# shelves_expander_v10.net
KiCad netlist of a schematic drawn in EAGLE
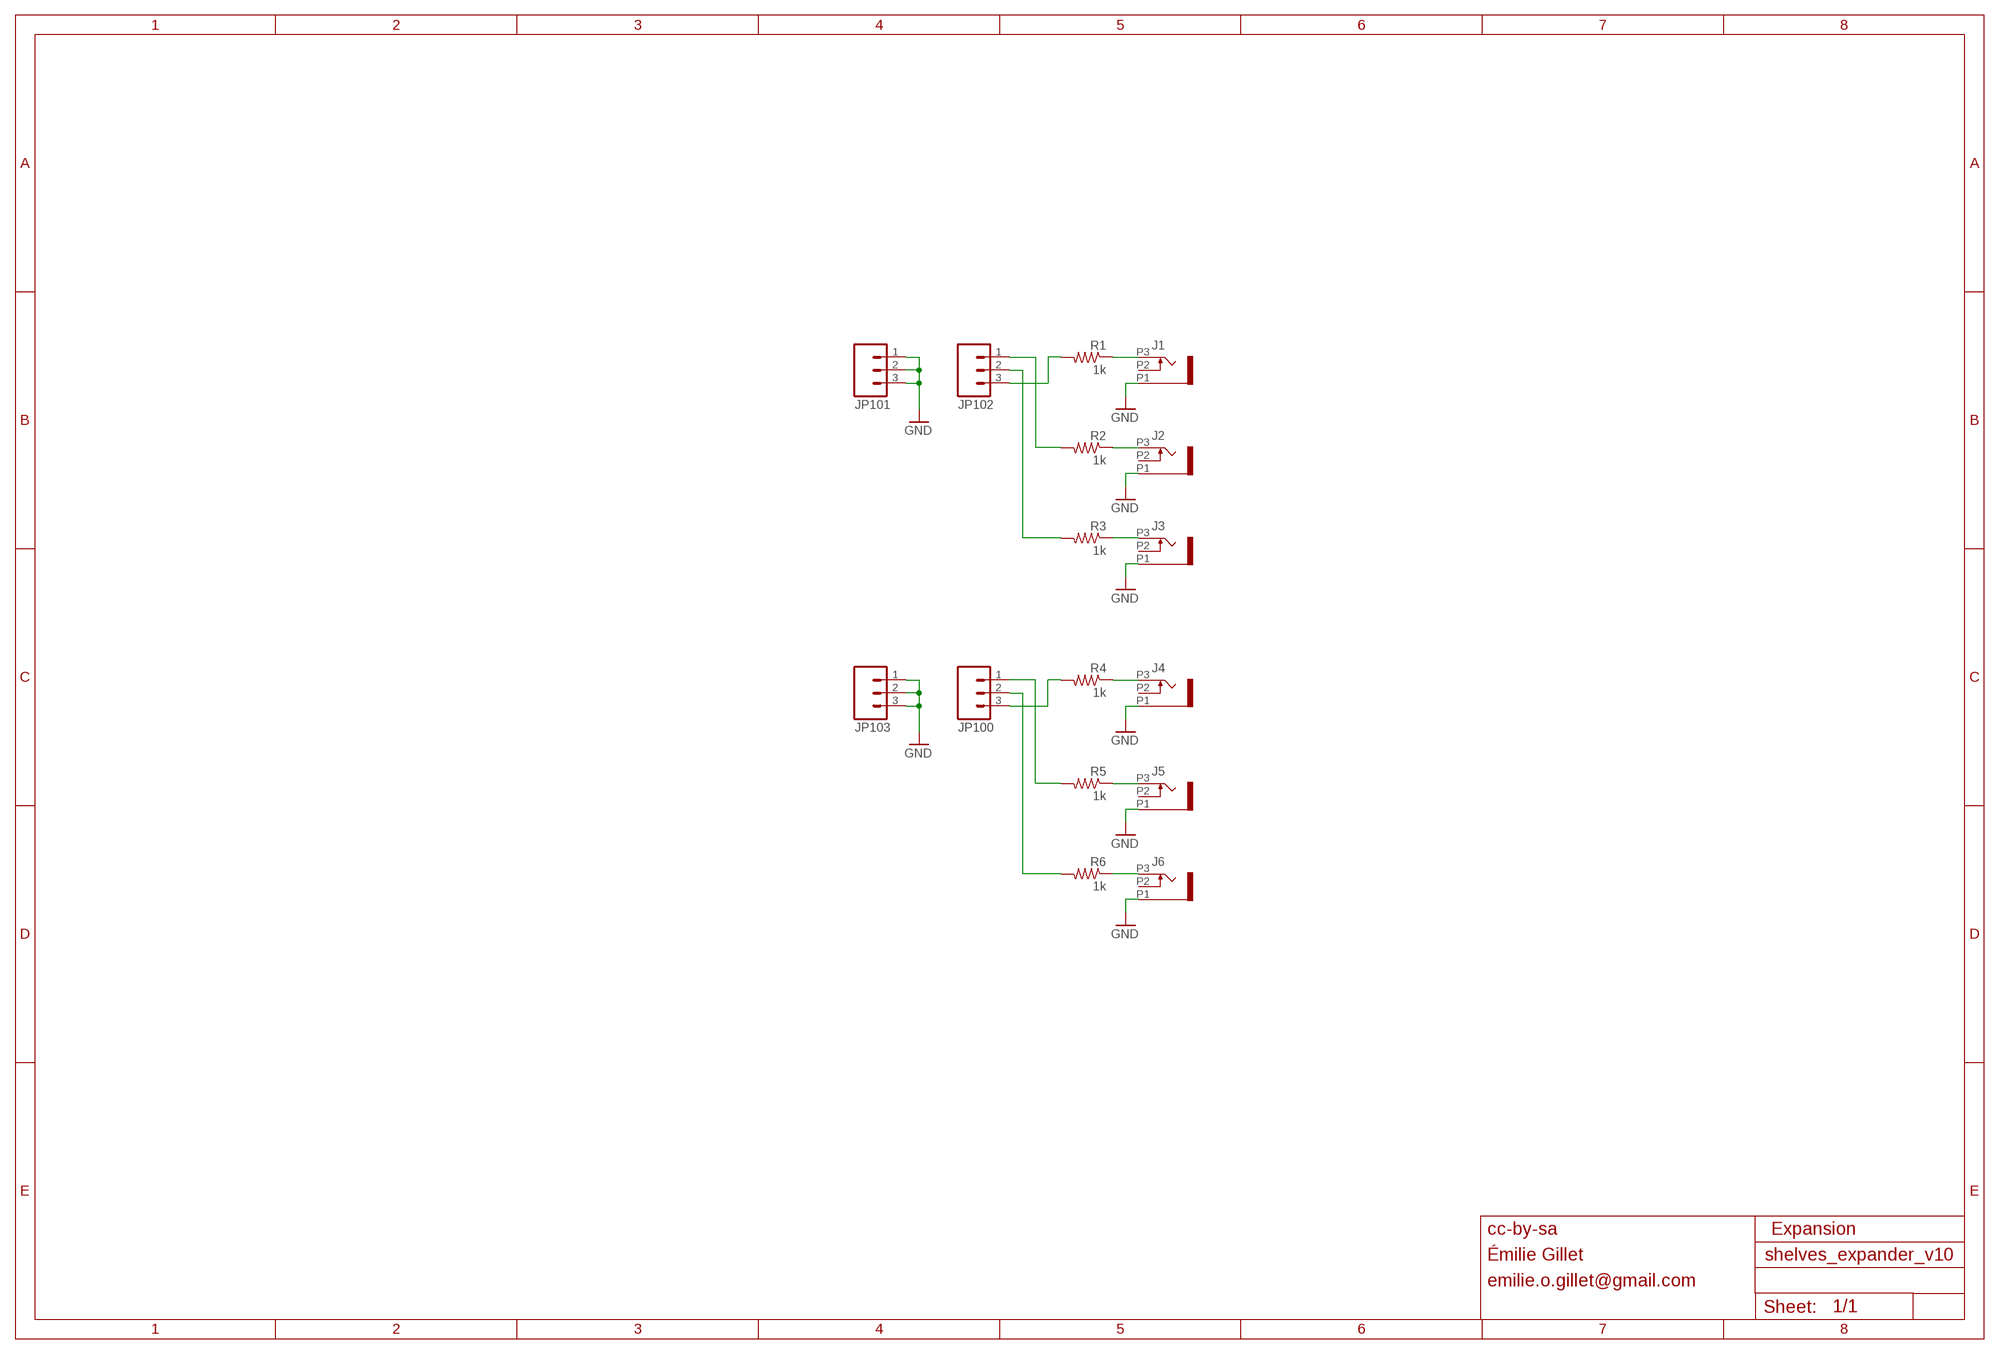
[diagram p0: schematic, sheet 1]

(export (version "E")
  (design (tool "Eeschema 10.0.6"))
  (components
    (comp (ref "J1")
      (value "PJ301_THONKICONN6")
      (footprint "eagle-import:WQP_PJ_301M6")
      (libsource (lib "eagle-import") (part "PJ301_THONKICONN6"))
    )
    (comp (ref "J2")
      (value "PJ301_THONKICONN6")
      (footprint "eagle-import:WQP_PJ_301M6")
      (libsource (lib "eagle-import") (part "PJ301_THONKICONN6"))
    )
    (comp (ref "J3")
      (value "PJ301_THONKICONN6")
      (footprint "eagle-import:WQP_PJ_301M6")
      (libsource (lib "eagle-import") (part "PJ301_THONKICONN6"))
    )
    (comp (ref "J4")
      (value "PJ301_THONKICONN6")
      (footprint "eagle-import:WQP_PJ_301M6")
      (libsource (lib "eagle-import") (part "PJ301_THONKICONN6"))
    )
    (comp (ref "J5")
      (value "PJ301_THONKICONN6")
      (footprint "eagle-import:WQP_PJ_301M6")
      (libsource (lib "eagle-import") (part "PJ301_THONKICONN6"))
    )
    (comp (ref "J6")
      (value "PJ301_THONKICONN6")
      (footprint "eagle-import:WQP_PJ_301M6")
      (libsource (lib "eagle-import") (part "PJ301_THONKICONN6"))
    )
    (comp (ref "JP100")
      (value "M03PTH")
      (footprint "eagle-import:1X03")
      (libsource (lib "eagle-import") (part "M03PTH"))
    )
    (comp (ref "JP101")
      (value "M03PTH")
      (footprint "eagle-import:1X03")
      (libsource (lib "eagle-import") (part "M03PTH"))
    )
    (comp (ref "JP102")
      (value "M03PTH")
      (footprint "eagle-import:1X03")
      (libsource (lib "eagle-import") (part "M03PTH"))
    )
    (comp (ref "JP103")
      (value "M03PTH")
      (footprint "eagle-import:1X03")
      (libsource (lib "eagle-import") (part "M03PTH"))
    )
    (comp (ref "R1")
      (value "1k")
      (footprint "eagle-import:R0603")
      (libsource (lib "eagle-import") (part "R-US_R0603"))
    )
    (comp (ref "R2")
      (value "1k")
      (footprint "eagle-import:R0603")
      (libsource (lib "eagle-import") (part "R-US_R0603"))
    )
    (comp (ref "R3")
      (value "1k")
      (footprint "eagle-import:R0603")
      (libsource (lib "eagle-import") (part "R-US_R0603"))
    )
    (comp (ref "R4")
      (value "1k")
      (footprint "eagle-import:R0603")
      (libsource (lib "eagle-import") (part "R-US_R0603"))
    )
    (comp (ref "R5")
      (value "1k")
      (footprint "eagle-import:R0603")
      (libsource (lib "eagle-import") (part "R-US_R0603"))
    )
    (comp (ref "R6")
      (value "1k")
      (footprint "eagle-import:R0603")
      (libsource (lib "eagle-import") (part "R-US_R0603"))
    )
  )
  (nets
    (net (code "1") (name "GND") (class "Default")
      (node (ref "J1") (pin "P1") (pinfunction "1_P1") (pintype "passive"))
      (node (ref "J2") (pin "P1") (pinfunction "1_P1") (pintype "passive"))
      (node (ref "J3") (pin "P1") (pinfunction "1_P1") (pintype "passive"))
      (node (ref "J4") (pin "P1") (pinfunction "1_P1") (pintype "passive"))
      (node (ref "J5") (pin "P1") (pinfunction "1_P1") (pintype "passive"))
      (node (ref "J6") (pin "P1") (pinfunction "1_P1") (pintype "passive"))
      (node (ref "JP101") (pin "1") (pinfunction "1_1") (pintype "passive"))
      (node (ref "JP101") (pin "2") (pinfunction "2_2") (pintype "passive"))
      (node (ref "JP101") (pin "3") (pinfunction "3_3") (pintype "passive"))
      (node (ref "JP103") (pin "1") (pinfunction "1_1") (pintype "passive"))
      (node (ref "JP103") (pin "2") (pinfunction "2_2") (pintype "passive"))
      (node (ref "JP103") (pin "3") (pinfunction "3_3") (pintype "passive"))
    )
    (net (code "2") (name "Net-(J1-3)") (class "Default")
      (node (ref "J1") (pin "P3") (pinfunction "3_P3") (pintype "passive"))
      (node (ref "R1") (pin "1") (pinfunction "1_1") (pintype "passive"))
    )
    (net (code "3") (name "Net-(J2-3)") (class "Default")
      (node (ref "J2") (pin "P3") (pinfunction "3_P3") (pintype "passive"))
      (node (ref "R2") (pin "1") (pinfunction "1_1") (pintype "passive"))
    )
    (net (code "4") (name "Net-(J3-3)") (class "Default")
      (node (ref "J3") (pin "P3") (pinfunction "3_P3") (pintype "passive"))
      (node (ref "R3") (pin "1") (pinfunction "1_1") (pintype "passive"))
    )
    (net (code "5") (name "Net-(J4-3)") (class "Default")
      (node (ref "J4") (pin "P3") (pinfunction "3_P3") (pintype "passive"))
      (node (ref "R4") (pin "1") (pinfunction "1_1") (pintype "passive"))
    )
    (net (code "6") (name "Net-(J5-3)") (class "Default")
      (node (ref "J5") (pin "P3") (pinfunction "3_P3") (pintype "passive"))
      (node (ref "R5") (pin "1") (pinfunction "1_1") (pintype "passive"))
    )
    (net (code "7") (name "Net-(J6-3)") (class "Default")
      (node (ref "J6") (pin "P3") (pinfunction "3_P3") (pintype "passive"))
      (node (ref "R6") (pin "1") (pinfunction "1_1") (pintype "passive"))
    )
    (net (code "8") (name "Net-(JP100-Pad1)") (class "Default")
      (node (ref "JP100") (pin "1") (pinfunction "1_1") (pintype "passive"))
      (node (ref "R5") (pin "2") (pinfunction "2_2") (pintype "passive"))
    )
    (net (code "9") (name "Net-(JP100-Pad2)") (class "Default")
      (node (ref "JP100") (pin "2") (pinfunction "2_2") (pintype "passive"))
      (node (ref "R6") (pin "2") (pinfunction "2_2") (pintype "passive"))
    )
    (net (code "10") (name "Net-(JP100-Pad3)") (class "Default")
      (node (ref "JP100") (pin "3") (pinfunction "3_3") (pintype "passive"))
      (node (ref "R4") (pin "2") (pinfunction "2_2") (pintype "passive"))
    )
    (net (code "11") (name "Net-(JP102-Pad1)") (class "Default")
      (node (ref "JP102") (pin "1") (pinfunction "1_1") (pintype "passive"))
      (node (ref "R2") (pin "2") (pinfunction "2_2") (pintype "passive"))
    )
    (net (code "12") (name "Net-(JP102-Pad2)") (class "Default")
      (node (ref "JP102") (pin "2") (pinfunction "2_2") (pintype "passive"))
      (node (ref "R3") (pin "2") (pinfunction "2_2") (pintype "passive"))
    )
    (net (code "13") (name "Net-(JP102-Pad3)") (class "Default")
      (node (ref "JP102") (pin "3") (pinfunction "3_3") (pintype "passive"))
      (node (ref "R1") (pin "2") (pinfunction "2_2") (pintype "passive"))
    )
    (net (code "14") (name "unconnected-(J1-2-PadP2)") (class "Default")
      (node (ref "J1") (pin "P2") (pinfunction "2_P2") (pintype "passive"))
    )
    (net (code "15") (name "unconnected-(J2-2-PadP2)") (class "Default")
      (node (ref "J2") (pin "P2") (pinfunction "2_P2") (pintype "passive"))
    )
    (net (code "16") (name "unconnected-(J3-2-PadP2)") (class "Default")
      (node (ref "J3") (pin "P2") (pinfunction "2_P2") (pintype "passive"))
    )
    (net (code "17") (name "unconnected-(J4-2-PadP2)") (class "Default")
      (node (ref "J4") (pin "P2") (pinfunction "2_P2") (pintype "passive"))
    )
    (net (code "18") (name "unconnected-(J5-2-PadP2)") (class "Default")
      (node (ref "J5") (pin "P2") (pinfunction "2_P2") (pintype "passive"))
    )
    (net (code "19") (name "unconnected-(J6-2-PadP2)") (class "Default")
      (node (ref "J6") (pin "P2") (pinfunction "2_P2") (pintype "passive"))
    )
  )
)
